# Linefollower_STM32.net
KiCad netlist of a schematic drawn in EAGLE
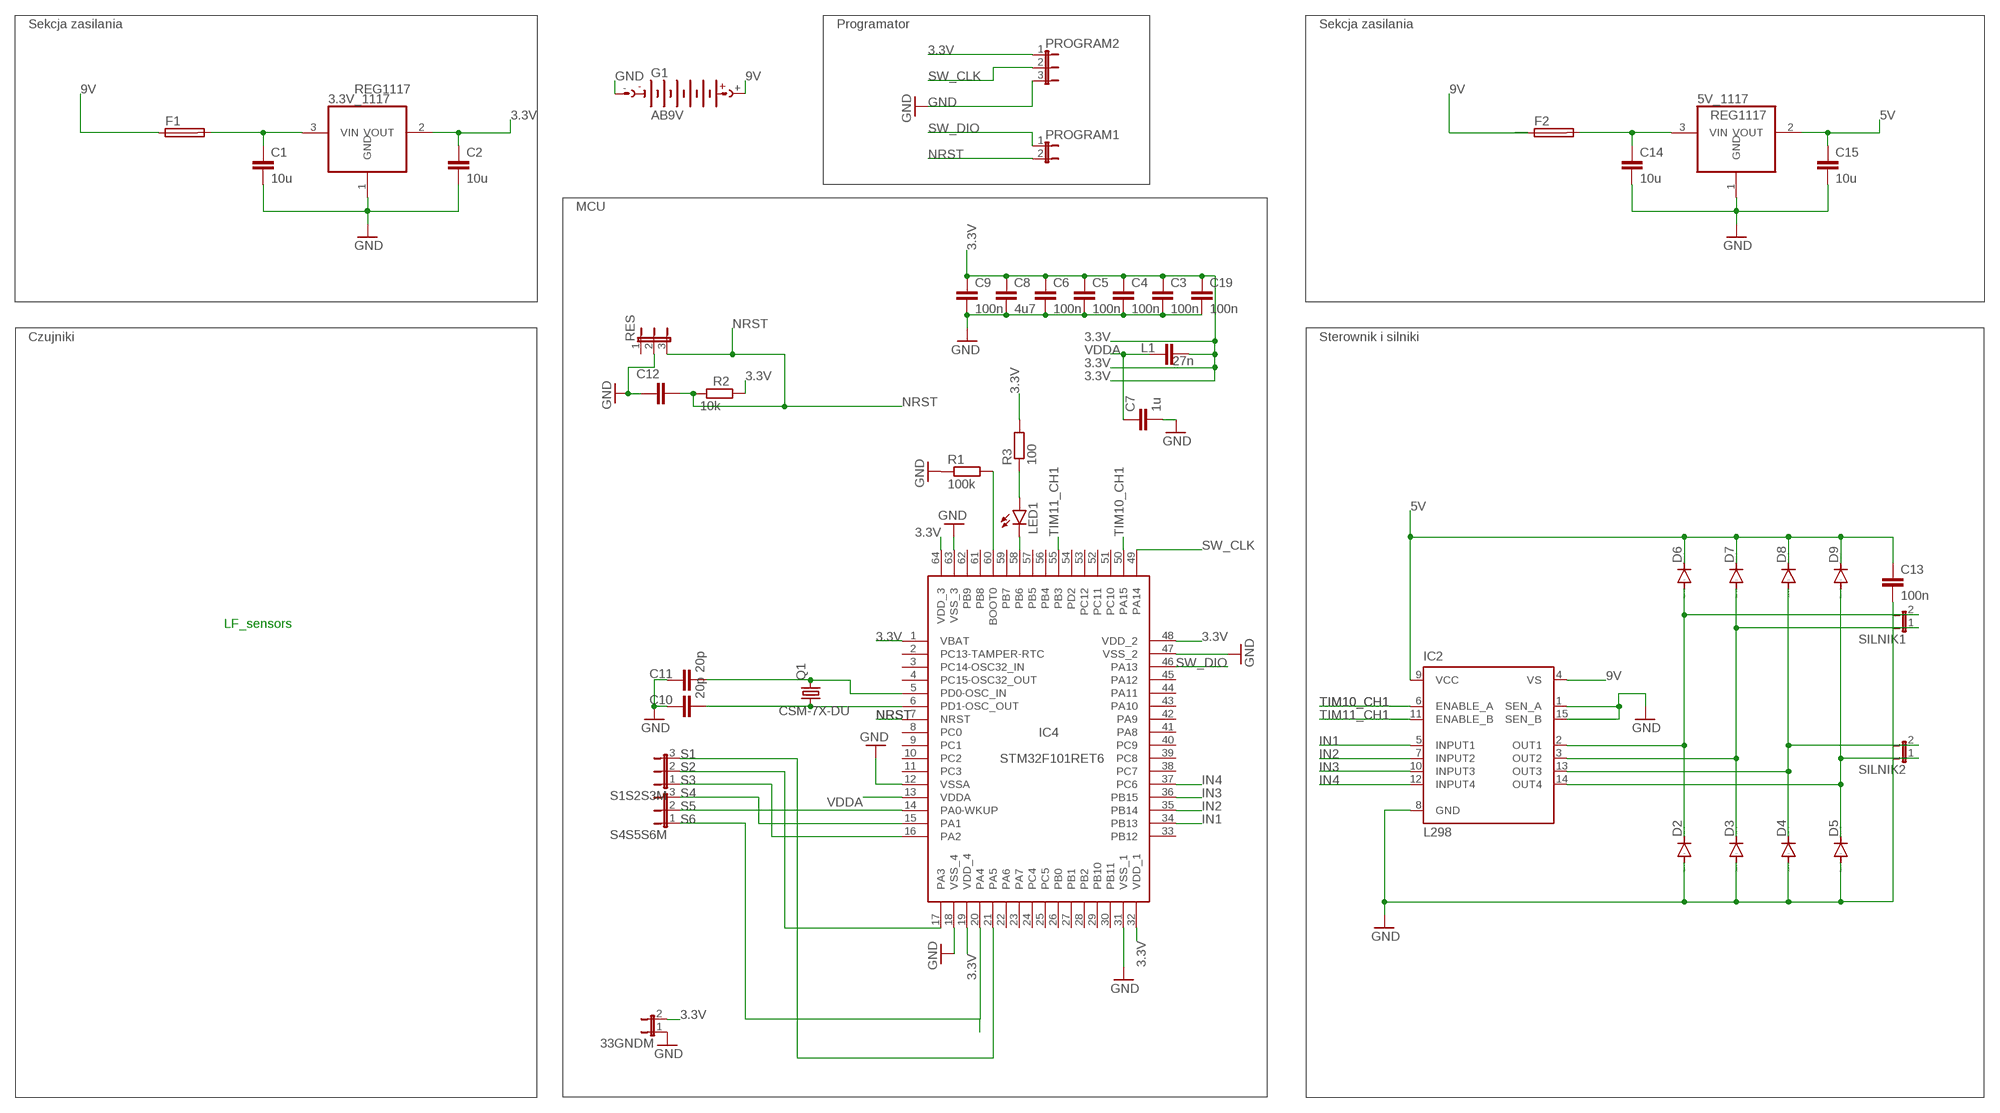
[diagram p0: schematic, sheet 1]

(export (version "E")
  (design (tool "Eeschema 10.0.6"))
  (components
    (comp (ref "3.3V_1117")
      (value "REG1117")
      (footprint "eagle-import:SOT223")
      (libsource (lib "eagle-import") (part "REG1117"))
    )
    (comp (ref "5V_1117")
      (value "REG1117")
      (footprint "eagle-import:SOT223")
      (libsource (lib "eagle-import") (part "REG1117"))
    )
    (comp (ref "33GNDM")
      (value "JP1E")
      (footprint "eagle-import:JP1")
      (libsource (lib "eagle-import") (part "JP1E"))
    )
    (comp (ref "C1")
      (value "10u")
      (footprint "eagle-import:C0805")
      (libsource (lib "eagle-import") (part "C-EUC0805"))
    )
    (comp (ref "C2")
      (value "10u")
      (footprint "eagle-import:C0805")
      (libsource (lib "eagle-import") (part "C-EUC0805"))
    )
    (comp (ref "C3")
      (value "100n")
      (footprint "eagle-import:C0805")
      (libsource (lib "eagle-import") (part "C-EUC0805"))
    )
    (comp (ref "C4")
      (value "100n")
      (footprint "eagle-import:C0805")
      (libsource (lib "eagle-import") (part "C-EUC0805"))
    )
    (comp (ref "C5")
      (value "100n")
      (footprint "eagle-import:C0805")
      (libsource (lib "eagle-import") (part "C-EUC0805"))
    )
    (comp (ref "C6")
      (value "100n")
      (footprint "eagle-import:C0805")
      (libsource (lib "eagle-import") (part "C-EUC0805"))
    )
    (comp (ref "C7")
      (value "1u")
      (footprint "eagle-import:C0805")
      (libsource (lib "eagle-import") (part "C-EUC0805"))
    )
    (comp (ref "C8")
      (value "4u7")
      (footprint "eagle-import:C0805")
      (libsource (lib "eagle-import") (part "C-EUC0805"))
    )
    (comp (ref "C9")
      (value "100n")
      (footprint "eagle-import:C0805")
      (libsource (lib "eagle-import") (part "C-EUC0805"))
    )
    (comp (ref "C10")
      (value "20p")
      (footprint "eagle-import:C0805")
      (libsource (lib "eagle-import") (part "C-EUC0805"))
    )
    (comp (ref "C11")
      (value "20p")
      (footprint "eagle-import:C0805")
      (libsource (lib "eagle-import") (part "C-EUC0805"))
    )
    (comp (ref "C12")
      (value "C-EUC0805")
      (footprint "eagle-import:C0805")
      (libsource (lib "eagle-import") (part "C-EUC0805"))
    )
    (comp (ref "C13")
      (value "100n")
      (footprint "eagle-import:C0805")
      (libsource (lib "eagle-import") (part "C-EUC0805"))
    )
    (comp (ref "C14")
      (value "10u")
      (footprint "eagle-import:C0805")
      (libsource (lib "eagle-import") (part "C-EUC0805"))
    )
    (comp (ref "C15")
      (value "10u")
      (footprint "eagle-import:C0805")
      (libsource (lib "eagle-import") (part "C-EUC0805"))
    )
    (comp (ref "C19")
      (value "100n")
      (footprint "eagle-import:C0805")
      (libsource (lib "eagle-import") (part "C-EUC0805"))
    )
    (comp (ref "D2")
      (value "DIODE-DO214AA")
      (footprint "eagle-import:DO214AA")
      (libsource (lib "eagle-import") (part "DIODE-DO214AA"))
    )
    (comp (ref "D3")
      (value "DIODE-DO214AA")
      (footprint "eagle-import:DO214AA")
      (libsource (lib "eagle-import") (part "DIODE-DO214AA"))
    )
    (comp (ref "D4")
      (value "DIODE-DO214AA")
      (footprint "eagle-import:DO214AA")
      (libsource (lib "eagle-import") (part "DIODE-DO214AA"))
    )
    (comp (ref "D5")
      (value "DIODE-DO214AA")
      (footprint "eagle-import:DO214AA")
      (libsource (lib "eagle-import") (part "DIODE-DO214AA"))
    )
    (comp (ref "D6")
      (value "DIODE-DO214AA")
      (footprint "eagle-import:DO214AA")
      (libsource (lib "eagle-import") (part "DIODE-DO214AA"))
    )
    (comp (ref "D7")
      (value "DIODE-DO214AA")
      (footprint "eagle-import:DO214AA")
      (libsource (lib "eagle-import") (part "DIODE-DO214AA"))
    )
    (comp (ref "D8")
      (value "DIODE-DO214AA")
      (footprint "eagle-import:DO214AA")
      (libsource (lib "eagle-import") (part "DIODE-DO214AA"))
    )
    (comp (ref "D9")
      (value "DIODE-DO214AA")
      (footprint "eagle-import:DO214AA")
      (libsource (lib "eagle-import") (part "DIODE-DO214AA"))
    )
    (comp (ref "F1")
      (value "TE5")
      (footprint "eagle-import:TE5")
      (libsource (lib "eagle-import") (part "TE5"))
    )
    (comp (ref "F2")
      (value "TE5")
      (footprint "eagle-import:TE5")
      (libsource (lib "eagle-import") (part "TE5"))
    )
    (comp (ref "G1")
      (value "AB9V")
      (footprint "eagle-import:AB9V")
      (libsource (lib "eagle-import") (part "AB9V"))
    )
    (comp (ref "IC2")
      (value "L298")
      (footprint "eagle-import:MULTIWATT-15")
      (fields (field (name "MPN") "L298N"))
      (libsource (lib "eagle-import") (part "L298"))
    )
    (comp (ref "IC4")
      (value "STM32F101RET6")
      (footprint "eagle-import:QFP50P1200X1200X160-64N")
      (fields (field (name "MOUSER_PART_NUMBER") "511-STM32F101RET6"))
      (libsource (lib "eagle-import") (part "STM32F101RET6"))
    )
    (comp (ref "L1")
      (value "27n")
      (footprint "eagle-import:C0805")
      (libsource (lib "eagle-import") (part "C-EUC0805"))
    )
    (comp (ref "LED1")
      (value "LEDSML1206")
      (footprint "eagle-import:SML1206")
      (libsource (lib "eagle-import") (part "LEDSML1206"))
    )
    (comp (ref "PROGRAM1")
      (value "JP1E")
      (footprint "eagle-import:JP1")
      (libsource (lib "eagle-import") (part "JP1E"))
    )
    (comp (ref "PROGRAM2")
      (value "JP2E")
      (footprint "eagle-import:JP2")
      (libsource (lib "eagle-import") (part "JP2E"))
    )
    (comp (ref "Q1")
      (value "CSM-7X-DU")
      (footprint "eagle-import:CSM-7X-DU")
      (libsource (lib "eagle-import") (part "CSM-7X-DU"))
    )
    (comp (ref "R1")
      (value "100k")
      (footprint "eagle-import:R0805")
      (libsource (lib "eagle-import") (part "R-EU_R0805"))
    )
    (comp (ref "R2")
      (value "10k")
      (footprint "eagle-import:R0805")
      (libsource (lib "eagle-import") (part "R-EU_R0805"))
    )
    (comp (ref "R3")
      (value "100")
      (footprint "eagle-import:R0805")
      (libsource (lib "eagle-import") (part "R-EU_R0805"))
    )
    (comp (ref "RES")
      (value "JP2E")
      (footprint "eagle-import:JP2")
      (libsource (lib "eagle-import") (part "JP2E"))
    )
    (comp (ref "S1S2S3M")
      (value "JP2E")
      (footprint "eagle-import:JP2")
      (libsource (lib "eagle-import") (part "JP2E"))
    )
    (comp (ref "S4S5S6M")
      (value "JP2E")
      (footprint "eagle-import:JP2")
      (libsource (lib "eagle-import") (part "JP2E"))
    )
    (comp (ref "SILNIK1")
      (value "JP1E")
      (footprint "eagle-import:JP1")
      (libsource (lib "eagle-import") (part "JP1E"))
    )
    (comp (ref "SILNIK2")
      (value "JP1E")
      (footprint "eagle-import:JP1")
      (libsource (lib "eagle-import") (part "JP1E"))
    )
  )
  (nets
    (net (code "1") (name "/3.3V") (class "Default")
      (node (ref "3.3V_1117") (pin "2") (pinfunction "VOUT_2") (pintype "output"))
      (node (ref "33GNDM") (pin "2") (pinfunction "2_2") (pintype "passive"))
      (node (ref "C19") (pin "1") (pinfunction "1_1") (pintype "passive"))
      (node (ref "C2") (pin "1") (pinfunction "1_1") (pintype "passive"))
      (node (ref "C3") (pin "1") (pinfunction "1_1") (pintype "passive"))
      (node (ref "C4") (pin "1") (pinfunction "1_1") (pintype "passive"))
      (node (ref "C5") (pin "1") (pinfunction "1_1") (pintype "passive"))
      (node (ref "C6") (pin "1") (pinfunction "1_1") (pintype "passive"))
      (node (ref "C8") (pin "1") (pinfunction "1_1") (pintype "passive"))
      (node (ref "C9") (pin "1") (pinfunction "1_1") (pintype "passive"))
      (node (ref "IC4") (pin "1") (pinfunction "VBAT_1") (pintype "bidirectional"))
      (node (ref "IC4") (pin "19") (pinfunction "VDD_4_19") (pintype "bidirectional"))
      (node (ref "IC4") (pin "32") (pinfunction "VDD_1_32") (pintype "bidirectional"))
      (node (ref "IC4") (pin "48") (pinfunction "VDD_2_48") (pintype "bidirectional"))
      (node (ref "IC4") (pin "64") (pinfunction "VDD_3_64") (pintype "bidirectional"))
      (node (ref "L1") (pin "2") (pinfunction "2_2") (pintype "passive"))
      (node (ref "PROGRAM2") (pin "1") (pinfunction "1_1") (pintype "passive"))
      (node (ref "R2") (pin "2") (pinfunction "2_2") (pintype "passive"))
      (node (ref "R3") (pin "2") (pinfunction "2_2") (pintype "passive"))
    )
    (net (code "2") (name "/5V") (class "Default")
      (node (ref "5V_1117") (pin "2") (pinfunction "VOUT_2") (pintype "output"))
      (node (ref "C13") (pin "1") (pinfunction "1_1") (pintype "passive"))
      (node (ref "C15") (pin "1") (pinfunction "1_1") (pintype "passive"))
      (node (ref "D6") (pin "C") (pinfunction "C_C") (pintype "passive"))
      (node (ref "D7") (pin "C") (pinfunction "C_C") (pintype "passive"))
      (node (ref "D8") (pin "C") (pinfunction "C_C") (pintype "passive"))
      (node (ref "D9") (pin "C") (pinfunction "C_C") (pintype "passive"))
      (node (ref "IC2") (pin "9") (pinfunction "VCC_9") (pintype "power_in"))
    )
    (net (code "3") (name "/9V") (class "Default")
      (node (ref "F1") (pin "1") (pinfunction "1_1") (pintype "passive"))
      (node (ref "F2") (pin "1") (pinfunction "1_1") (pintype "passive"))
      (node (ref "G1") (pin "+") (pinfunction "+_+") (pintype "passive"))
      (node (ref "IC2") (pin "4") (pinfunction "VS_4") (pintype "power_in"))
    )
    (net (code "4") (name "/IN1") (class "Default")
      (node (ref "IC2") (pin "5") (pinfunction "INPUT1_5") (pintype "input"))
      (node (ref "IC4") (pin "34") (pinfunction "PB13_34") (pintype "bidirectional"))
    )
    (net (code "5") (name "/IN2") (class "Default")
      (node (ref "IC2") (pin "7") (pinfunction "INPUT2_7") (pintype "input"))
      (node (ref "IC4") (pin "35") (pinfunction "PB14_35") (pintype "bidirectional"))
    )
    (net (code "6") (name "/IN3") (class "Default")
      (node (ref "IC2") (pin "10") (pinfunction "INPUT3_10") (pintype "input"))
      (node (ref "IC4") (pin "36") (pinfunction "PB15_36") (pintype "bidirectional"))
    )
    (net (code "7") (name "/IN4") (class "Default")
      (node (ref "IC2") (pin "12") (pinfunction "INPUT4_12") (pintype "input"))
      (node (ref "IC4") (pin "37") (pinfunction "PC6_37") (pintype "bidirectional"))
    )
    (net (code "8") (name "/NRST") (class "Default")
      (node (ref "C12") (pin "2") (pinfunction "2_2") (pintype "passive"))
      (node (ref "IC4") (pin "7") (pinfunction "NRST_7") (pintype "bidirectional"))
      (node (ref "PROGRAM1") (pin "2") (pinfunction "2_2") (pintype "passive"))
      (node (ref "R2") (pin "1") (pinfunction "1_1") (pintype "passive"))
      (node (ref "RES") (pin "3") (pinfunction "3_3") (pintype "passive"))
    )
    (net (code "9") (name "/S1") (class "Default")
      (node (ref "IC4") (pin "21") (pinfunction "PA5_21") (pintype "bidirectional"))
      (node (ref "S1S2S3M") (pin "3") (pinfunction "3_3") (pintype "passive"))
    )
    (net (code "10") (name "/S2") (class "Default")
      (node (ref "IC4") (pin "17") (pinfunction "PA3_17") (pintype "bidirectional"))
      (node (ref "S1S2S3M") (pin "2") (pinfunction "2_2") (pintype "passive"))
    )
    (net (code "11") (name "/S3") (class "Default")
      (node (ref "IC4") (pin "16") (pinfunction "PA2_16") (pintype "bidirectional"))
      (node (ref "S1S2S3M") (pin "1") (pinfunction "1_1") (pintype "passive"))
    )
    (net (code "12") (name "/S4") (class "Default")
      (node (ref "IC4") (pin "15") (pinfunction "PA1_15") (pintype "bidirectional"))
      (node (ref "S4S5S6M") (pin "3") (pinfunction "3_3") (pintype "passive"))
    )
    (net (code "13") (name "/S5") (class "Default")
      (node (ref "IC4") (pin "14") (pinfunction "PA0-WKUP_14") (pintype "bidirectional"))
      (node (ref "S4S5S6M") (pin "2") (pinfunction "2_2") (pintype "passive"))
    )
    (net (code "14") (name "/S6") (class "Default")
      (node (ref "IC4") (pin "20") (pinfunction "PA4_20") (pintype "bidirectional"))
      (node (ref "S4S5S6M") (pin "1") (pinfunction "1_1") (pintype "passive"))
    )
    (net (code "15") (name "/SW_CLK") (class "Default")
      (node (ref "IC4") (pin "49") (pinfunction "PA14_49") (pintype "bidirectional"))
      (node (ref "PROGRAM2") (pin "2") (pinfunction "2_2") (pintype "passive"))
    )
    (net (code "16") (name "/SW_DIO") (class "Default")
      (node (ref "IC4") (pin "46") (pinfunction "PA13_46") (pintype "bidirectional"))
      (node (ref "PROGRAM1") (pin "1") (pinfunction "1_1") (pintype "passive"))
    )
    (net (code "17") (name "/TIM10_CH1") (class "Default")
      (node (ref "IC2") (pin "6") (pinfunction "ENABLE_A_6") (pintype "input"))
      (node (ref "IC4") (pin "50") (pinfunction "PA15_50") (pintype "bidirectional"))
    )
    (net (code "18") (name "/TIM11_CH1") (class "Default")
      (node (ref "IC2") (pin "11") (pinfunction "ENABLE_B_11") (pintype "input"))
      (node (ref "IC4") (pin "55") (pinfunction "PB3_55") (pintype "bidirectional"))
    )
    (net (code "19") (name "/VDDA") (class "Default")
      (node (ref "C7") (pin "1") (pinfunction "1_1") (pintype "passive"))
      (node (ref "IC4") (pin "13") (pinfunction "VDDA_13") (pintype "bidirectional"))
      (node (ref "L1") (pin "1") (pinfunction "1_1") (pintype "passive"))
    )
    (net (code "20") (name "GND") (class "Default")
      (node (ref "3.3V_1117") (pin "1") (pinfunction "GND_1") (pintype "power_in"))
      (node (ref "33GNDM") (pin "1") (pinfunction "1_1") (pintype "passive"))
      (node (ref "5V_1117") (pin "1") (pinfunction "GND_1") (pintype "power_in"))
      (node (ref "C1") (pin "2") (pinfunction "2_2") (pintype "passive"))
      (node (ref "C10") (pin "1") (pinfunction "1_1") (pintype "passive"))
      (node (ref "C11") (pin "1") (pinfunction "1_1") (pintype "passive"))
      (node (ref "C12") (pin "1") (pinfunction "1_1") (pintype "passive"))
      (node (ref "C13") (pin "2") (pinfunction "2_2") (pintype "passive"))
      (node (ref "C14") (pin "2") (pinfunction "2_2") (pintype "passive"))
      (node (ref "C15") (pin "2") (pinfunction "2_2") (pintype "passive"))
      (node (ref "C19") (pin "2") (pinfunction "2_2") (pintype "passive"))
      (node (ref "C2") (pin "2") (pinfunction "2_2") (pintype "passive"))
      (node (ref "C3") (pin "2") (pinfunction "2_2") (pintype "passive"))
      (node (ref "C4") (pin "2") (pinfunction "2_2") (pintype "passive"))
      (node (ref "C5") (pin "2") (pinfunction "2_2") (pintype "passive"))
      (node (ref "C6") (pin "2") (pinfunction "2_2") (pintype "passive"))
      (node (ref "C7") (pin "2") (pinfunction "2_2") (pintype "passive"))
      (node (ref "C8") (pin "2") (pinfunction "2_2") (pintype "passive"))
      (node (ref "C9") (pin "2") (pinfunction "2_2") (pintype "passive"))
      (node (ref "D2") (pin "A") (pinfunction "A_A") (pintype "passive"))
      (node (ref "D3") (pin "A") (pinfunction "A_A") (pintype "passive"))
      (node (ref "D4") (pin "A") (pinfunction "A_A") (pintype "passive"))
      (node (ref "D5") (pin "A") (pinfunction "A_A") (pintype "passive"))
      (node (ref "G1") (pin "-") (pinfunction "-_-") (pintype "passive"))
      (node (ref "IC2") (pin "1") (pinfunction "SEN_A_1") (pintype "input"))
      (node (ref "IC2") (pin "15") (pinfunction "SEN_B_15") (pintype "input"))
      (node (ref "IC2") (pin "8") (pinfunction "GND_8") (pintype "power_in"))
      (node (ref "IC4") (pin "12") (pinfunction "VSSA_12") (pintype "bidirectional"))
      (node (ref "IC4") (pin "18") (pinfunction "VSS_4_18") (pintype "bidirectional"))
      (node (ref "IC4") (pin "31") (pinfunction "VSS_1_31") (pintype "bidirectional"))
      (node (ref "IC4") (pin "47") (pinfunction "VSS_2_47") (pintype "bidirectional"))
      (node (ref "IC4") (pin "63") (pinfunction "VSS_3_63") (pintype "bidirectional"))
      (node (ref "PROGRAM2") (pin "3") (pinfunction "3_3") (pintype "passive"))
      (node (ref "R1") (pin "1") (pinfunction "1_1") (pintype "passive"))
      (node (ref "RES") (pin "2") (pinfunction "2_2") (pintype "passive"))
    )
    (net (code "21") (name "Net-(3.3V_1117-VIN)") (class "Default")
      (node (ref "3.3V_1117") (pin "3") (pinfunction "VIN_3") (pintype "input"))
      (node (ref "C1") (pin "1") (pinfunction "1_1") (pintype "passive"))
      (node (ref "F1") (pin "2") (pinfunction "2_2") (pintype "passive"))
    )
    (net (code "22") (name "Net-(5V_1117-VIN)") (class "Default")
      (node (ref "5V_1117") (pin "3") (pinfunction "VIN_3") (pintype "input"))
      (node (ref "C14") (pin "1") (pinfunction "1_1") (pintype "passive"))
      (node (ref "F2") (pin "2") (pinfunction "2_2") (pintype "passive"))
    )
    (net (code "23") (name "Net-(IC2-OUT1)") (class "Default")
      (node (ref "D2") (pin "C") (pinfunction "C_C") (pintype "passive"))
      (node (ref "D6") (pin "A") (pinfunction "A_A") (pintype "passive"))
      (node (ref "IC2") (pin "2") (pinfunction "OUT1_2") (pintype "output"))
      (node (ref "SILNIK1") (pin "2") (pinfunction "2_2") (pintype "passive"))
    )
    (net (code "24") (name "Net-(IC2-OUT2)") (class "Default")
      (node (ref "D3") (pin "C") (pinfunction "C_C") (pintype "passive"))
      (node (ref "D7") (pin "A") (pinfunction "A_A") (pintype "passive"))
      (node (ref "IC2") (pin "3") (pinfunction "OUT2_3") (pintype "output"))
      (node (ref "SILNIK1") (pin "1") (pinfunction "1_1") (pintype "passive"))
    )
    (net (code "25") (name "Net-(IC2-OUT3)") (class "Default")
      (node (ref "D4") (pin "C") (pinfunction "C_C") (pintype "passive"))
      (node (ref "D8") (pin "A") (pinfunction "A_A") (pintype "passive"))
      (node (ref "IC2") (pin "13") (pinfunction "OUT3_13") (pintype "output"))
      (node (ref "SILNIK2") (pin "2") (pinfunction "2_2") (pintype "passive"))
    )
    (net (code "26") (name "Net-(IC2-OUT4)") (class "Default")
      (node (ref "D5") (pin "C") (pinfunction "C_C") (pintype "passive"))
      (node (ref "D9") (pin "A") (pinfunction "A_A") (pintype "passive"))
      (node (ref "IC2") (pin "14") (pinfunction "OUT4_14") (pintype "output"))
      (node (ref "SILNIK2") (pin "1") (pinfunction "1_1") (pintype "passive"))
    )
    (net (code "27") (name "Net-(IC4-BOOT0)") (class "Default")
      (node (ref "IC4") (pin "60") (pinfunction "BOOT0_60") (pintype "bidirectional"))
      (node (ref "R1") (pin "2") (pinfunction "2_2") (pintype "passive"))
    )
    (net (code "28") (name "Net-(IC4-PB6)") (class "Default")
      (node (ref "IC4") (pin "58") (pinfunction "PB6_58") (pintype "bidirectional"))
      (node (ref "LED1") (pin "C") (pinfunction "C_C") (pintype "passive"))
    )
    (net (code "29") (name "Net-(IC4-PD0-OSC_IN)") (class "Default")
      (node (ref "C11") (pin "2") (pinfunction "2_2") (pintype "passive"))
      (node (ref "IC4") (pin "5") (pinfunction "PD0-OSC_IN_5") (pintype "bidirectional"))
      (node (ref "Q1") (pin "2") (pinfunction "2_2") (pintype "passive"))
    )
    (net (code "30") (name "Net-(IC4-PD1-OSC_OUT)") (class "Default")
      (node (ref "C10") (pin "2") (pinfunction "2_2") (pintype "passive"))
      (node (ref "IC4") (pin "6") (pinfunction "PD1-OSC_OUT_6") (pintype "bidirectional"))
      (node (ref "Q1") (pin "1") (pinfunction "1_1") (pintype "passive"))
    )
    (net (code "31") (name "Net-(LED1-PadA)") (class "Default")
      (node (ref "LED1") (pin "A") (pinfunction "A_A") (pintype "passive"))
      (node (ref "R3") (pin "1") (pinfunction "1_1") (pintype "passive"))
    )
    (net (code "32") (name "unconnected-(IC4-PA6-Pad22)") (class "Default")
      (node (ref "IC4") (pin "22") (pinfunction "PA6_22") (pintype "bidirectional"))
    )
    (net (code "33") (name "unconnected-(IC4-PA7-Pad23)") (class "Default")
      (node (ref "IC4") (pin "23") (pinfunction "PA7_23") (pintype "bidirectional"))
    )
    (net (code "34") (name "unconnected-(IC4-PA8-Pad41)") (class "Default")
      (node (ref "IC4") (pin "41") (pinfunction "PA8_41") (pintype "bidirectional"))
    )
    (net (code "35") (name "unconnected-(IC4-PA9-Pad42)") (class "Default")
      (node (ref "IC4") (pin "42") (pinfunction "PA9_42") (pintype "bidirectional"))
    )
    (net (code "36") (name "unconnected-(IC4-PA10-Pad43)") (class "Default")
      (node (ref "IC4") (pin "43") (pinfunction "PA10_43") (pintype "bidirectional"))
    )
    (net (code "37") (name "unconnected-(IC4-PA11-Pad44)") (class "Default")
      (node (ref "IC4") (pin "44") (pinfunction "PA11_44") (pintype "bidirectional"))
    )
    (net (code "38") (name "unconnected-(IC4-PA12-Pad45)") (class "Default")
      (node (ref "IC4") (pin "45") (pinfunction "PA12_45") (pintype "bidirectional"))
    )
    (net (code "39") (name "unconnected-(IC4-PB0-Pad26)") (class "Default")
      (node (ref "IC4") (pin "26") (pinfunction "PB0_26") (pintype "bidirectional"))
    )
    (net (code "40") (name "unconnected-(IC4-PB1-Pad27)") (class "Default")
      (node (ref "IC4") (pin "27") (pinfunction "PB1_27") (pintype "bidirectional"))
    )
    (net (code "41") (name "unconnected-(IC4-PB2-Pad28)") (class "Default")
      (node (ref "IC4") (pin "28") (pinfunction "PB2_28") (pintype "bidirectional"))
    )
    (net (code "42") (name "unconnected-(IC4-PB4-Pad56)") (class "Default")
      (node (ref "IC4") (pin "56") (pinfunction "PB4_56") (pintype "bidirectional"))
    )
    (net (code "43") (name "unconnected-(IC4-PB5-Pad57)") (class "Default")
      (node (ref "IC4") (pin "57") (pinfunction "PB5_57") (pintype "bidirectional"))
    )
    (net (code "44") (name "unconnected-(IC4-PB7-Pad59)") (class "Default")
      (node (ref "IC4") (pin "59") (pinfunction "PB7_59") (pintype "bidirectional"))
    )
    (net (code "45") (name "unconnected-(IC4-PB8-Pad61)") (class "Default")
      (node (ref "IC4") (pin "61") (pinfunction "PB8_61") (pintype "bidirectional"))
    )
    (net (code "46") (name "unconnected-(IC4-PB9-Pad62)") (class "Default")
      (node (ref "IC4") (pin "62") (pinfunction "PB9_62") (pintype "bidirectional"))
    )
    (net (code "47") (name "unconnected-(IC4-PB10-Pad29)") (class "Default")
      (node (ref "IC4") (pin "29") (pinfunction "PB10_29") (pintype "bidirectional"))
    )
    (net (code "48") (name "unconnected-(IC4-PB11-Pad30)") (class "Default")
      (node (ref "IC4") (pin "30") (pinfunction "PB11_30") (pintype "bidirectional"))
    )
    (net (code "49") (name "unconnected-(IC4-PB12-Pad33)") (class "Default")
      (node (ref "IC4") (pin "33") (pinfunction "PB12_33") (pintype "bidirectional"))
    )
    (net (code "50") (name "unconnected-(IC4-PC0-Pad8)") (class "Default")
      (node (ref "IC4") (pin "8") (pinfunction "PC0_8") (pintype "bidirectional"))
    )
    (net (code "51") (name "unconnected-(IC4-PC1-Pad9)") (class "Default")
      (node (ref "IC4") (pin "9") (pinfunction "PC1_9") (pintype "bidirectional"))
    )
    (net (code "52") (name "unconnected-(IC4-PC2-Pad10)") (class "Default")
      (node (ref "IC4") (pin "10") (pinfunction "PC2_10") (pintype "bidirectional"))
    )
    (net (code "53") (name "unconnected-(IC4-PC3-Pad11)") (class "Default")
      (node (ref "IC4") (pin "11") (pinfunction "PC3_11") (pintype "bidirectional"))
    )
    (net (code "54") (name "unconnected-(IC4-PC4-Pad24)") (class "Default")
      (node (ref "IC4") (pin "24") (pinfunction "PC4_24") (pintype "bidirectional"))
    )
    (net (code "55") (name "unconnected-(IC4-PC5-Pad25)") (class "Default")
      (node (ref "IC4") (pin "25") (pinfunction "PC5_25") (pintype "bidirectional"))
    )
    (net (code "56") (name "unconnected-(IC4-PC7-Pad38)") (class "Default")
      (node (ref "IC4") (pin "38") (pinfunction "PC7_38") (pintype "bidirectional"))
    )
    (net (code "57") (name "unconnected-(IC4-PC8-Pad39)") (class "Default")
      (node (ref "IC4") (pin "39") (pinfunction "PC8_39") (pintype "bidirectional"))
    )
    (net (code "58") (name "unconnected-(IC4-PC9-Pad40)") (class "Default")
      (node (ref "IC4") (pin "40") (pinfunction "PC9_40") (pintype "bidirectional"))
    )
    (net (code "59") (name "unconnected-(IC4-PC10-Pad51)") (class "Default")
      (node (ref "IC4") (pin "51") (pinfunction "PC10_51") (pintype "bidirectional"))
    )
    (net (code "60") (name "unconnected-(IC4-PC11-Pad52)") (class "Default")
      (node (ref "IC4") (pin "52") (pinfunction "PC11_52") (pintype "bidirectional"))
    )
    (net (code "61") (name "unconnected-(IC4-PC12-Pad53)") (class "Default")
      (node (ref "IC4") (pin "53") (pinfunction "PC12_53") (pintype "bidirectional"))
    )
    (net (code "62") (name "unconnected-(IC4-PC13-TAMPER-RTC-Pad2)") (class "Default")
      (node (ref "IC4") (pin "2") (pinfunction "PC13-TAMPER-RTC_2") (pintype "bidirectional"))
    )
    (net (code "63") (name "unconnected-(IC4-PC14-OSC32_IN-Pad3)") (class "Default")
      (node (ref "IC4") (pin "3") (pinfunction "PC14-OSC32_IN_3") (pintype "bidirectional"))
    )
    (net (code "64") (name "unconnected-(IC4-PC15-OSC32_OUT-Pad4)") (class "Default")
      (node (ref "IC4") (pin "4") (pinfunction "PC15-OSC32_OUT_4") (pintype "bidirectional"))
    )
    (net (code "65") (name "unconnected-(IC4-PD2-Pad54)") (class "Default")
      (node (ref "IC4") (pin "54") (pinfunction "PD2_54") (pintype "bidirectional"))
    )
    (net (code "66") (name "unconnected-(RES-Pad1)") (class "Default")
      (node (ref "RES") (pin "1") (pinfunction "1_1") (pintype "passive"))
    )
  )
)
